# yacc2buss.net
KiCad netlist of a schematic drawn in EAGLE
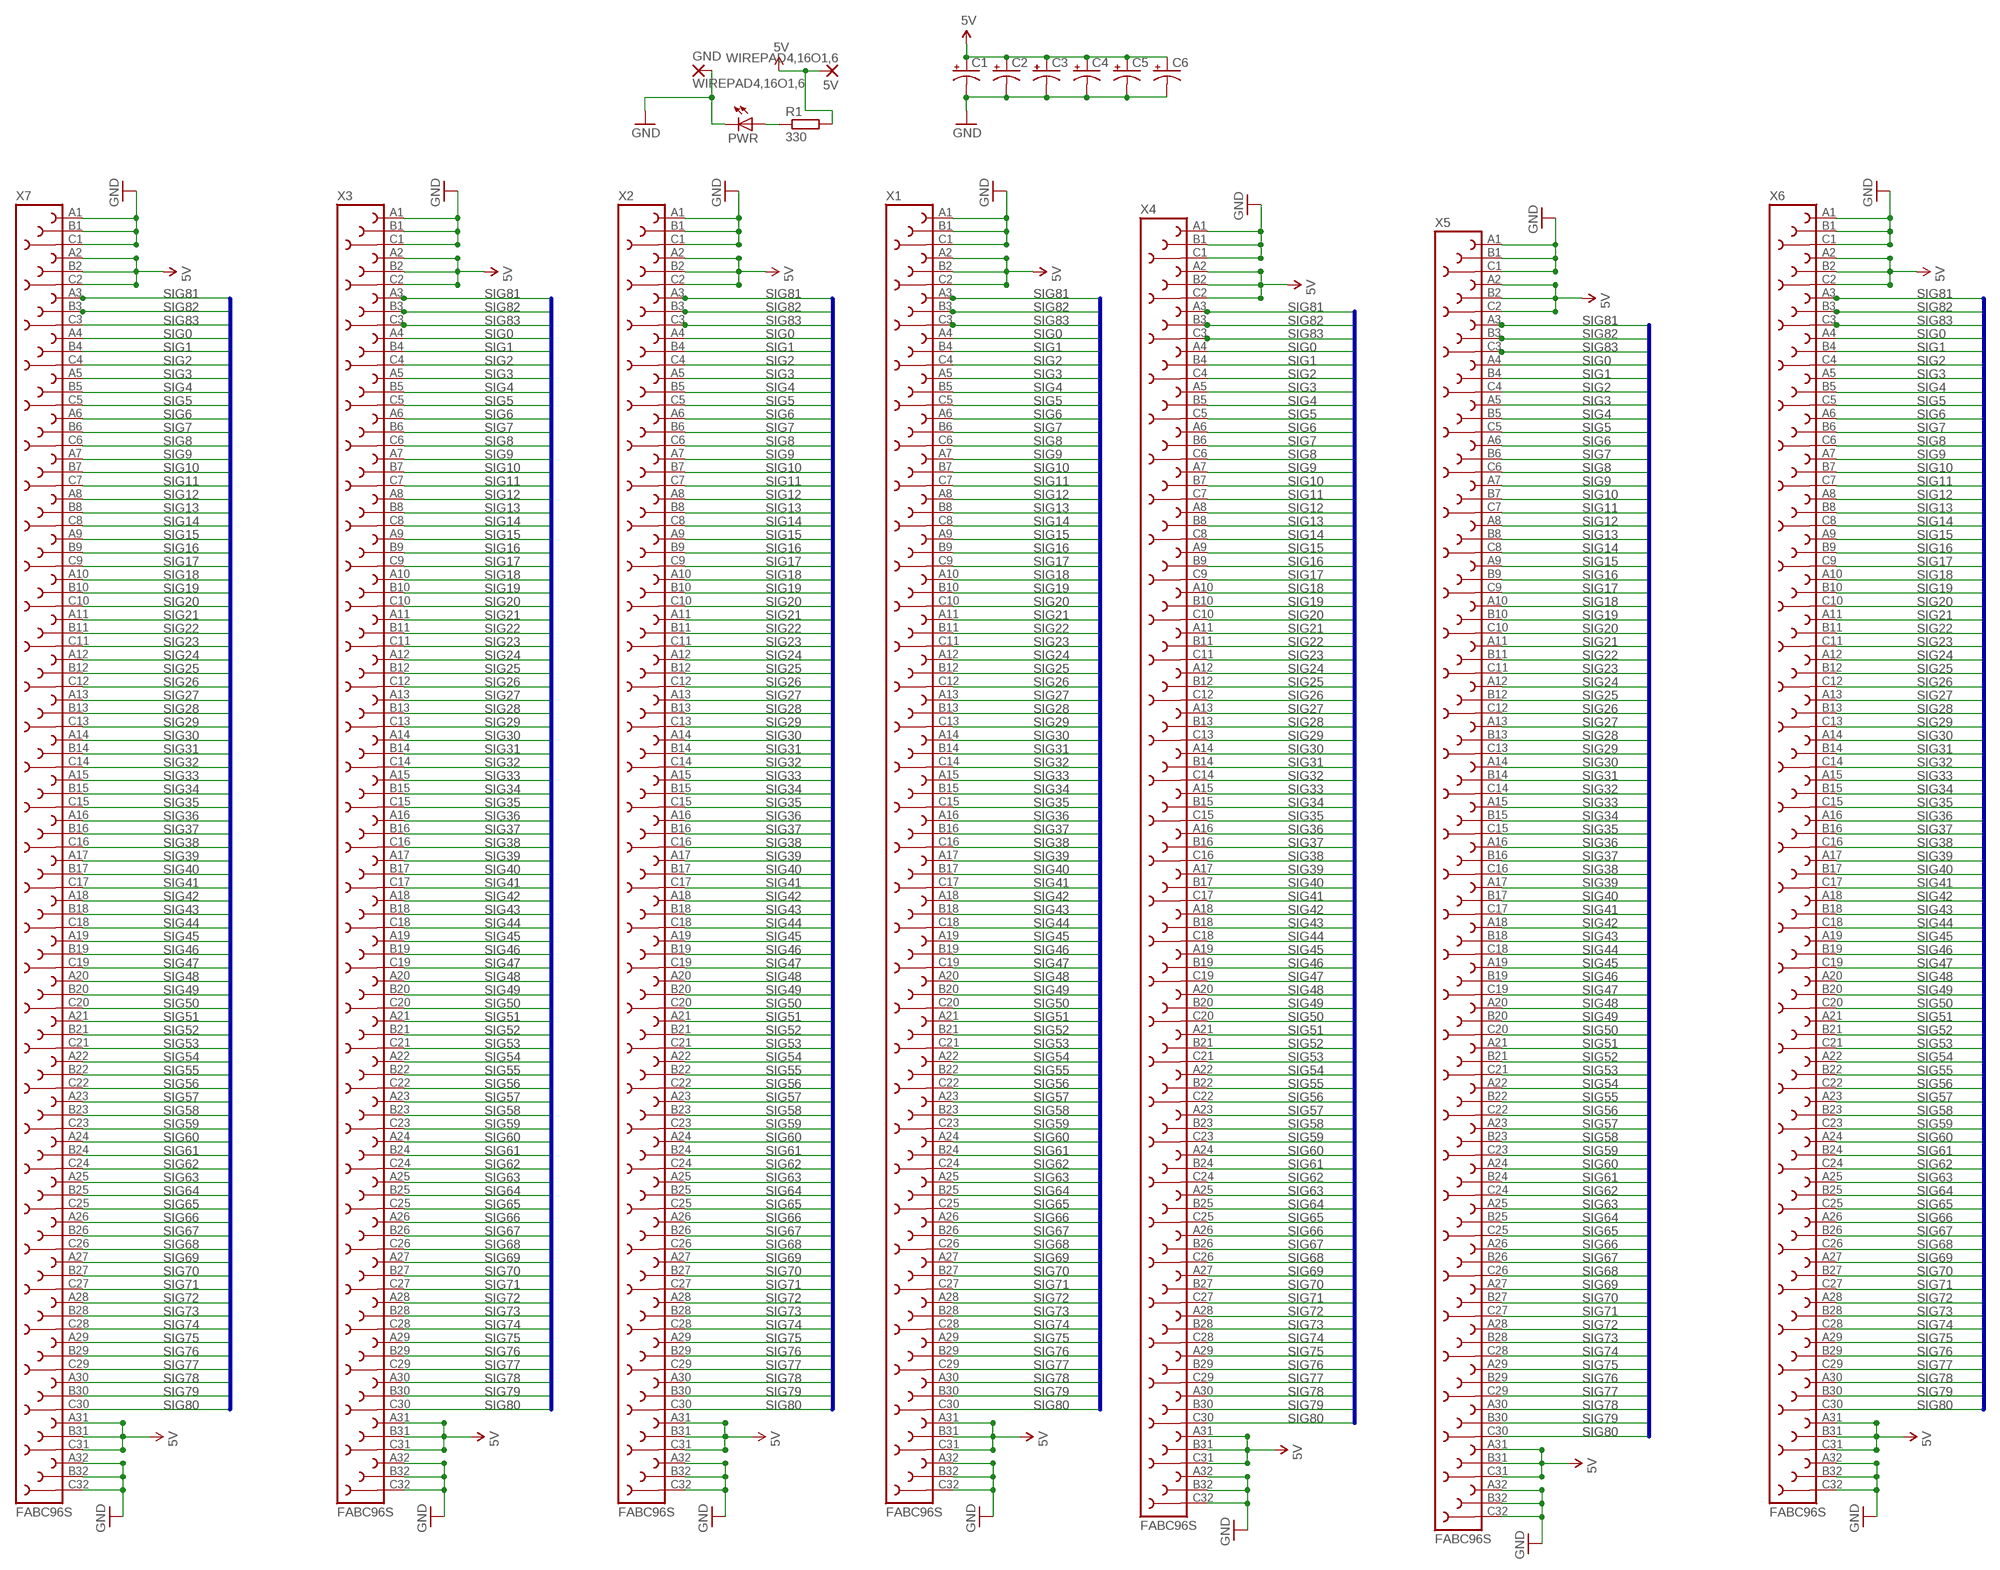
[diagram p0: schematic, sheet 1]

(export (version "E")
  (design (tool "Eeschema 10.0.6"))
  (components
    (comp (ref "5V")
      (value "WIREPAD4,16O1,6")
      (footprint "eagle-import:4,16O1,6")
      (libsource (lib "eagle-import") (part "WIREPAD4,16O1,6"))
    )
    (comp (ref "C1")
      (value "CPOL-USE5-6")
      (footprint "eagle-import:E5-6")
      (libsource (lib "eagle-import") (part "CPOL-USE5-6"))
    )
    (comp (ref "C2")
      (value "CPOL-USE5-6")
      (footprint "eagle-import:E5-6")
      (libsource (lib "eagle-import") (part "CPOL-USE5-6"))
    )
    (comp (ref "C3")
      (value "CPOL-USE5-6")
      (footprint "eagle-import:E5-6")
      (libsource (lib "eagle-import") (part "CPOL-USE5-6"))
    )
    (comp (ref "C4")
      (value "CPOL-USE5-6")
      (footprint "eagle-import:E5-6")
      (libsource (lib "eagle-import") (part "CPOL-USE5-6"))
    )
    (comp (ref "C5")
      (value "CPOL-USE5-6")
      (footprint "eagle-import:E5-6")
      (libsource (lib "eagle-import") (part "CPOL-USE5-6"))
    )
    (comp (ref "C6")
      (value "CPOL-USE5-6")
      (footprint "eagle-import:E5-6")
      (libsource (lib "eagle-import") (part "CPOL-USE5-6"))
    )
    (comp (ref "GND")
      (value "WIREPAD4,16O1,6")
      (footprint "eagle-import:4,16O1,6")
      (libsource (lib "eagle-import") (part "WIREPAD4,16O1,6"))
    )
    (comp (ref "PWR")
      (value "LED5MM")
      (footprint "eagle-import:LED5MM")
      (libsource (lib "eagle-import") (part "LED5MM"))
    )
    (comp (ref "R1")
      (value "330")
      (footprint "eagle-import:0207_10")
      (libsource (lib "eagle-import") (part "R0207/10"))
    )
    (comp (ref "X1")
      (value "FABC96S")
      (footprint "eagle-import:FABC96S")
      (libsource (lib "eagle-import") (part "FABC96S"))
    )
    (comp (ref "X2")
      (value "FABC96S")
      (footprint "eagle-import:FABC96S")
      (libsource (lib "eagle-import") (part "FABC96S"))
    )
    (comp (ref "X3")
      (value "FABC96S")
      (footprint "eagle-import:FABC96S")
      (libsource (lib "eagle-import") (part "FABC96S"))
    )
    (comp (ref "X4")
      (value "FABC96S")
      (footprint "eagle-import:FABC96S")
      (libsource (lib "eagle-import") (part "FABC96S"))
    )
    (comp (ref "X5")
      (value "FABC96S")
      (footprint "eagle-import:FABC96S")
      (libsource (lib "eagle-import") (part "FABC96S"))
    )
    (comp (ref "X6")
      (value "FABC96S")
      (footprint "eagle-import:FABC96S")
      (libsource (lib "eagle-import") (part "FABC96S"))
    )
    (comp (ref "X7")
      (value "FABC96S")
      (footprint "eagle-import:FABC96S")
      (libsource (lib "eagle-import") (part "FABC96S"))
    )
  )
  (nets
    (net (code "1") (name "/SIG0") (class "Default")
      (node (ref "X1") (pin "A4") (pinfunction "A4_A4") (pintype "passive"))
      (node (ref "X2") (pin "A4") (pinfunction "A4_A4") (pintype "passive"))
      (node (ref "X3") (pin "A4") (pinfunction "A4_A4") (pintype "passive"))
      (node (ref "X4") (pin "A4") (pinfunction "A4_A4") (pintype "passive"))
      (node (ref "X5") (pin "A4") (pinfunction "A4_A4") (pintype "passive"))
      (node (ref "X6") (pin "A4") (pinfunction "A4_A4") (pintype "passive"))
      (node (ref "X7") (pin "A4") (pinfunction "A4_A4") (pintype "passive"))
    )
    (net (code "2") (name "/SIG1") (class "Default")
      (node (ref "X1") (pin "B4") (pinfunction "B4_B4") (pintype "passive"))
      (node (ref "X2") (pin "B4") (pinfunction "B4_B4") (pintype "passive"))
      (node (ref "X3") (pin "B4") (pinfunction "B4_B4") (pintype "passive"))
      (node (ref "X4") (pin "B4") (pinfunction "B4_B4") (pintype "passive"))
      (node (ref "X5") (pin "B4") (pinfunction "B4_B4") (pintype "passive"))
      (node (ref "X6") (pin "B4") (pinfunction "B4_B4") (pintype "passive"))
      (node (ref "X7") (pin "B4") (pinfunction "B4_B4") (pintype "passive"))
    )
    (net (code "3") (name "/SIG2") (class "Default")
      (node (ref "X1") (pin "C4") (pinfunction "C4_C4") (pintype "passive"))
      (node (ref "X2") (pin "C4") (pinfunction "C4_C4") (pintype "passive"))
      (node (ref "X3") (pin "C4") (pinfunction "C4_C4") (pintype "passive"))
      (node (ref "X4") (pin "C4") (pinfunction "C4_C4") (pintype "passive"))
      (node (ref "X5") (pin "C4") (pinfunction "C4_C4") (pintype "passive"))
      (node (ref "X6") (pin "C4") (pinfunction "C4_C4") (pintype "passive"))
      (node (ref "X7") (pin "C4") (pinfunction "C4_C4") (pintype "passive"))
    )
    (net (code "4") (name "/SIG3") (class "Default")
      (node (ref "X1") (pin "A5") (pinfunction "A5_A5") (pintype "passive"))
      (node (ref "X2") (pin "A5") (pinfunction "A5_A5") (pintype "passive"))
      (node (ref "X3") (pin "A5") (pinfunction "A5_A5") (pintype "passive"))
      (node (ref "X4") (pin "A5") (pinfunction "A5_A5") (pintype "passive"))
      (node (ref "X5") (pin "A5") (pinfunction "A5_A5") (pintype "passive"))
      (node (ref "X6") (pin "A5") (pinfunction "A5_A5") (pintype "passive"))
      (node (ref "X7") (pin "A5") (pinfunction "A5_A5") (pintype "passive"))
    )
    (net (code "5") (name "/SIG4") (class "Default")
      (node (ref "X1") (pin "B5") (pinfunction "B5_B5") (pintype "passive"))
      (node (ref "X2") (pin "B5") (pinfunction "B5_B5") (pintype "passive"))
      (node (ref "X3") (pin "B5") (pinfunction "B5_B5") (pintype "passive"))
      (node (ref "X4") (pin "B5") (pinfunction "B5_B5") (pintype "passive"))
      (node (ref "X5") (pin "B5") (pinfunction "B5_B5") (pintype "passive"))
      (node (ref "X6") (pin "B5") (pinfunction "B5_B5") (pintype "passive"))
      (node (ref "X7") (pin "B5") (pinfunction "B5_B5") (pintype "passive"))
    )
    (net (code "6") (name "/SIG5") (class "Default")
      (node (ref "X1") (pin "C5") (pinfunction "C5_C5") (pintype "passive"))
      (node (ref "X2") (pin "C5") (pinfunction "C5_C5") (pintype "passive"))
      (node (ref "X3") (pin "C5") (pinfunction "C5_C5") (pintype "passive"))
      (node (ref "X4") (pin "C5") (pinfunction "C5_C5") (pintype "passive"))
      (node (ref "X5") (pin "C5") (pinfunction "C5_C5") (pintype "passive"))
      (node (ref "X6") (pin "C5") (pinfunction "C5_C5") (pintype "passive"))
      (node (ref "X7") (pin "C5") (pinfunction "C5_C5") (pintype "passive"))
    )
    (net (code "7") (name "/SIG6") (class "Default")
      (node (ref "X1") (pin "A6") (pinfunction "A6_A6") (pintype "passive"))
      (node (ref "X2") (pin "A6") (pinfunction "A6_A6") (pintype "passive"))
      (node (ref "X3") (pin "A6") (pinfunction "A6_A6") (pintype "passive"))
      (node (ref "X4") (pin "A6") (pinfunction "A6_A6") (pintype "passive"))
      (node (ref "X5") (pin "A6") (pinfunction "A6_A6") (pintype "passive"))
      (node (ref "X6") (pin "A6") (pinfunction "A6_A6") (pintype "passive"))
      (node (ref "X7") (pin "A6") (pinfunction "A6_A6") (pintype "passive"))
    )
    (net (code "8") (name "/SIG7") (class "Default")
      (node (ref "X1") (pin "B6") (pinfunction "B6_B6") (pintype "passive"))
      (node (ref "X2") (pin "B6") (pinfunction "B6_B6") (pintype "passive"))
      (node (ref "X3") (pin "B6") (pinfunction "B6_B6") (pintype "passive"))
      (node (ref "X4") (pin "B6") (pinfunction "B6_B6") (pintype "passive"))
      (node (ref "X5") (pin "B6") (pinfunction "B6_B6") (pintype "passive"))
      (node (ref "X6") (pin "B6") (pinfunction "B6_B6") (pintype "passive"))
      (node (ref "X7") (pin "B6") (pinfunction "B6_B6") (pintype "passive"))
    )
    (net (code "9") (name "/SIG8") (class "Default")
      (node (ref "X1") (pin "C6") (pinfunction "C6_C6") (pintype "passive"))
      (node (ref "X2") (pin "C6") (pinfunction "C6_C6") (pintype "passive"))
      (node (ref "X3") (pin "C6") (pinfunction "C6_C6") (pintype "passive"))
      (node (ref "X4") (pin "C6") (pinfunction "C6_C6") (pintype "passive"))
      (node (ref "X5") (pin "C6") (pinfunction "C6_C6") (pintype "passive"))
      (node (ref "X6") (pin "C6") (pinfunction "C6_C6") (pintype "passive"))
      (node (ref "X7") (pin "C6") (pinfunction "C6_C6") (pintype "passive"))
    )
    (net (code "10") (name "/SIG9") (class "Default")
      (node (ref "X1") (pin "A7") (pinfunction "A7_A7") (pintype "passive"))
      (node (ref "X2") (pin "A7") (pinfunction "A7_A7") (pintype "passive"))
      (node (ref "X3") (pin "A7") (pinfunction "A7_A7") (pintype "passive"))
      (node (ref "X4") (pin "A7") (pinfunction "A7_A7") (pintype "passive"))
      (node (ref "X5") (pin "A7") (pinfunction "A7_A7") (pintype "passive"))
      (node (ref "X6") (pin "A7") (pinfunction "A7_A7") (pintype "passive"))
      (node (ref "X7") (pin "A7") (pinfunction "A7_A7") (pintype "passive"))
    )
    (net (code "11") (name "/SIG10") (class "Default")
      (node (ref "X1") (pin "B7") (pinfunction "B7_B7") (pintype "passive"))
      (node (ref "X2") (pin "B7") (pinfunction "B7_B7") (pintype "passive"))
      (node (ref "X3") (pin "B7") (pinfunction "B7_B7") (pintype "passive"))
      (node (ref "X4") (pin "B7") (pinfunction "B7_B7") (pintype "passive"))
      (node (ref "X5") (pin "B7") (pinfunction "B7_B7") (pintype "passive"))
      (node (ref "X6") (pin "B7") (pinfunction "B7_B7") (pintype "passive"))
      (node (ref "X7") (pin "B7") (pinfunction "B7_B7") (pintype "passive"))
    )
    (net (code "12") (name "/SIG11") (class "Default")
      (node (ref "X1") (pin "C7") (pinfunction "C7_C7") (pintype "passive"))
      (node (ref "X2") (pin "C7") (pinfunction "C7_C7") (pintype "passive"))
      (node (ref "X3") (pin "C7") (pinfunction "C7_C7") (pintype "passive"))
      (node (ref "X4") (pin "C7") (pinfunction "C7_C7") (pintype "passive"))
      (node (ref "X5") (pin "C7") (pinfunction "C7_C7") (pintype "passive"))
      (node (ref "X6") (pin "C7") (pinfunction "C7_C7") (pintype "passive"))
      (node (ref "X7") (pin "C7") (pinfunction "C7_C7") (pintype "passive"))
    )
    (net (code "13") (name "/SIG12") (class "Default")
      (node (ref "X1") (pin "A8") (pinfunction "A8_A8") (pintype "passive"))
      (node (ref "X2") (pin "A8") (pinfunction "A8_A8") (pintype "passive"))
      (node (ref "X3") (pin "A8") (pinfunction "A8_A8") (pintype "passive"))
      (node (ref "X4") (pin "A8") (pinfunction "A8_A8") (pintype "passive"))
      (node (ref "X5") (pin "A8") (pinfunction "A8_A8") (pintype "passive"))
      (node (ref "X6") (pin "A8") (pinfunction "A8_A8") (pintype "passive"))
      (node (ref "X7") (pin "A8") (pinfunction "A8_A8") (pintype "passive"))
    )
    (net (code "14") (name "/SIG13") (class "Default")
      (node (ref "X1") (pin "B8") (pinfunction "B8_B8") (pintype "passive"))
      (node (ref "X2") (pin "B8") (pinfunction "B8_B8") (pintype "passive"))
      (node (ref "X3") (pin "B8") (pinfunction "B8_B8") (pintype "passive"))
      (node (ref "X4") (pin "B8") (pinfunction "B8_B8") (pintype "passive"))
      (node (ref "X5") (pin "B8") (pinfunction "B8_B8") (pintype "passive"))
      (node (ref "X6") (pin "B8") (pinfunction "B8_B8") (pintype "passive"))
      (node (ref "X7") (pin "B8") (pinfunction "B8_B8") (pintype "passive"))
    )
    (net (code "15") (name "/SIG14") (class "Default")
      (node (ref "X1") (pin "C8") (pinfunction "C8_C8") (pintype "passive"))
      (node (ref "X2") (pin "C8") (pinfunction "C8_C8") (pintype "passive"))
      (node (ref "X3") (pin "C8") (pinfunction "C8_C8") (pintype "passive"))
      (node (ref "X4") (pin "C8") (pinfunction "C8_C8") (pintype "passive"))
      (node (ref "X5") (pin "C8") (pinfunction "C8_C8") (pintype "passive"))
      (node (ref "X6") (pin "C8") (pinfunction "C8_C8") (pintype "passive"))
      (node (ref "X7") (pin "C8") (pinfunction "C8_C8") (pintype "passive"))
    )
    (net (code "16") (name "/SIG15") (class "Default")
      (node (ref "X1") (pin "A9") (pinfunction "A9_A9") (pintype "passive"))
      (node (ref "X2") (pin "A9") (pinfunction "A9_A9") (pintype "passive"))
      (node (ref "X3") (pin "A9") (pinfunction "A9_A9") (pintype "passive"))
      (node (ref "X4") (pin "A9") (pinfunction "A9_A9") (pintype "passive"))
      (node (ref "X5") (pin "A9") (pinfunction "A9_A9") (pintype "passive"))
      (node (ref "X6") (pin "A9") (pinfunction "A9_A9") (pintype "passive"))
      (node (ref "X7") (pin "A9") (pinfunction "A9_A9") (pintype "passive"))
    )
    (net (code "17") (name "/SIG16") (class "Default")
      (node (ref "X1") (pin "B9") (pinfunction "B9_B9") (pintype "passive"))
      (node (ref "X2") (pin "B9") (pinfunction "B9_B9") (pintype "passive"))
      (node (ref "X3") (pin "B9") (pinfunction "B9_B9") (pintype "passive"))
      (node (ref "X4") (pin "B9") (pinfunction "B9_B9") (pintype "passive"))
      (node (ref "X5") (pin "B9") (pinfunction "B9_B9") (pintype "passive"))
      (node (ref "X6") (pin "B9") (pinfunction "B9_B9") (pintype "passive"))
      (node (ref "X7") (pin "B9") (pinfunction "B9_B9") (pintype "passive"))
    )
    (net (code "18") (name "/SIG17") (class "Default")
      (node (ref "X1") (pin "C9") (pinfunction "C9_C9") (pintype "passive"))
      (node (ref "X2") (pin "C9") (pinfunction "C9_C9") (pintype "passive"))
      (node (ref "X3") (pin "C9") (pinfunction "C9_C9") (pintype "passive"))
      (node (ref "X4") (pin "C9") (pinfunction "C9_C9") (pintype "passive"))
      (node (ref "X5") (pin "C9") (pinfunction "C9_C9") (pintype "passive"))
      (node (ref "X6") (pin "C9") (pinfunction "C9_C9") (pintype "passive"))
      (node (ref "X7") (pin "C9") (pinfunction "C9_C9") (pintype "passive"))
    )
    (net (code "19") (name "/SIG18") (class "Default")
      (node (ref "X1") (pin "A10") (pinfunction "A10_A10") (pintype "passive"))
      (node (ref "X2") (pin "A10") (pinfunction "A10_A10") (pintype "passive"))
      (node (ref "X3") (pin "A10") (pinfunction "A10_A10") (pintype "passive"))
      (node (ref "X4") (pin "A10") (pinfunction "A10_A10") (pintype "passive"))
      (node (ref "X5") (pin "A10") (pinfunction "A10_A10") (pintype "passive"))
      (node (ref "X6") (pin "A10") (pinfunction "A10_A10") (pintype "passive"))
      (node (ref "X7") (pin "A10") (pinfunction "A10_A10") (pintype "passive"))
    )
    (net (code "20") (name "/SIG19") (class "Default")
      (node (ref "X1") (pin "B10") (pinfunction "B10_B10") (pintype "passive"))
      (node (ref "X2") (pin "B10") (pinfunction "B10_B10") (pintype "passive"))
      (node (ref "X3") (pin "B10") (pinfunction "B10_B10") (pintype "passive"))
      (node (ref "X4") (pin "B10") (pinfunction "B10_B10") (pintype "passive"))
      (node (ref "X5") (pin "B10") (pinfunction "B10_B10") (pintype "passive"))
      (node (ref "X6") (pin "B10") (pinfunction "B10_B10") (pintype "passive"))
      (node (ref "X7") (pin "B10") (pinfunction "B10_B10") (pintype "passive"))
    )
    (net (code "21") (name "/SIG20") (class "Default")
      (node (ref "X1") (pin "C10") (pinfunction "C10_C10") (pintype "passive"))
      (node (ref "X2") (pin "C10") (pinfunction "C10_C10") (pintype "passive"))
      (node (ref "X3") (pin "C10") (pinfunction "C10_C10") (pintype "passive"))
      (node (ref "X4") (pin "C10") (pinfunction "C10_C10") (pintype "passive"))
      (node (ref "X5") (pin "C10") (pinfunction "C10_C10") (pintype "passive"))
      (node (ref "X6") (pin "C10") (pinfunction "C10_C10") (pintype "passive"))
      (node (ref "X7") (pin "C10") (pinfunction "C10_C10") (pintype "passive"))
    )
    (net (code "22") (name "/SIG21") (class "Default")
      (node (ref "X1") (pin "A11") (pinfunction "A11_A11") (pintype "passive"))
      (node (ref "X2") (pin "A11") (pinfunction "A11_A11") (pintype "passive"))
      (node (ref "X3") (pin "A11") (pinfunction "A11_A11") (pintype "passive"))
      (node (ref "X4") (pin "A11") (pinfunction "A11_A11") (pintype "passive"))
      (node (ref "X5") (pin "A11") (pinfunction "A11_A11") (pintype "passive"))
      (node (ref "X6") (pin "A11") (pinfunction "A11_A11") (pintype "passive"))
      (node (ref "X7") (pin "A11") (pinfunction "A11_A11") (pintype "passive"))
    )
    (net (code "23") (name "/SIG22") (class "Default")
      (node (ref "X1") (pin "B11") (pinfunction "B11_B11") (pintype "passive"))
      (node (ref "X2") (pin "B11") (pinfunction "B11_B11") (pintype "passive"))
      (node (ref "X3") (pin "B11") (pinfunction "B11_B11") (pintype "passive"))
      (node (ref "X4") (pin "B11") (pinfunction "B11_B11") (pintype "passive"))
      (node (ref "X5") (pin "B11") (pinfunction "B11_B11") (pintype "passive"))
      (node (ref "X6") (pin "B11") (pinfunction "B11_B11") (pintype "passive"))
      (node (ref "X7") (pin "B11") (pinfunction "B11_B11") (pintype "passive"))
    )
    (net (code "24") (name "/SIG23") (class "Default")
      (node (ref "X1") (pin "C11") (pinfunction "C11_C11") (pintype "passive"))
      (node (ref "X2") (pin "C11") (pinfunction "C11_C11") (pintype "passive"))
      (node (ref "X3") (pin "C11") (pinfunction "C11_C11") (pintype "passive"))
      (node (ref "X4") (pin "C11") (pinfunction "C11_C11") (pintype "passive"))
      (node (ref "X5") (pin "C11") (pinfunction "C11_C11") (pintype "passive"))
      (node (ref "X6") (pin "C11") (pinfunction "C11_C11") (pintype "passive"))
      (node (ref "X7") (pin "C11") (pinfunction "C11_C11") (pintype "passive"))
    )
    (net (code "25") (name "/SIG24") (class "Default")
      (node (ref "X1") (pin "A12") (pinfunction "A12_A12") (pintype "passive"))
      (node (ref "X2") (pin "A12") (pinfunction "A12_A12") (pintype "passive"))
      (node (ref "X3") (pin "A12") (pinfunction "A12_A12") (pintype "passive"))
      (node (ref "X4") (pin "A12") (pinfunction "A12_A12") (pintype "passive"))
      (node (ref "X5") (pin "A12") (pinfunction "A12_A12") (pintype "passive"))
      (node (ref "X6") (pin "A12") (pinfunction "A12_A12") (pintype "passive"))
      (node (ref "X7") (pin "A12") (pinfunction "A12_A12") (pintype "passive"))
    )
    (net (code "26") (name "/SIG25") (class "Default")
      (node (ref "X1") (pin "B12") (pinfunction "B12_B12") (pintype "passive"))
      (node (ref "X2") (pin "B12") (pinfunction "B12_B12") (pintype "passive"))
      (node (ref "X3") (pin "B12") (pinfunction "B12_B12") (pintype "passive"))
      (node (ref "X4") (pin "B12") (pinfunction "B12_B12") (pintype "passive"))
      (node (ref "X5") (pin "B12") (pinfunction "B12_B12") (pintype "passive"))
      (node (ref "X6") (pin "B12") (pinfunction "B12_B12") (pintype "passive"))
      (node (ref "X7") (pin "B12") (pinfunction "B12_B12") (pintype "passive"))
    )
    (net (code "27") (name "/SIG26") (class "Default")
      (node (ref "X1") (pin "C12") (pinfunction "C12_C12") (pintype "passive"))
      (node (ref "X2") (pin "C12") (pinfunction "C12_C12") (pintype "passive"))
      (node (ref "X3") (pin "C12") (pinfunction "C12_C12") (pintype "passive"))
      (node (ref "X4") (pin "C12") (pinfunction "C12_C12") (pintype "passive"))
      (node (ref "X5") (pin "C12") (pinfunction "C12_C12") (pintype "passive"))
      (node (ref "X6") (pin "C12") (pinfunction "C12_C12") (pintype "passive"))
      (node (ref "X7") (pin "C12") (pinfunction "C12_C12") (pintype "passive"))
    )
    (net (code "28") (name "/SIG27") (class "Default")
      (node (ref "X1") (pin "A13") (pinfunction "A13_A13") (pintype "passive"))
      (node (ref "X2") (pin "A13") (pinfunction "A13_A13") (pintype "passive"))
      (node (ref "X3") (pin "A13") (pinfunction "A13_A13") (pintype "passive"))
      (node (ref "X4") (pin "A13") (pinfunction "A13_A13") (pintype "passive"))
      (node (ref "X5") (pin "A13") (pinfunction "A13_A13") (pintype "passive"))
      (node (ref "X6") (pin "A13") (pinfunction "A13_A13") (pintype "passive"))
      (node (ref "X7") (pin "A13") (pinfunction "A13_A13") (pintype "passive"))
    )
    (net (code "29") (name "/SIG28") (class "Default")
      (node (ref "X1") (pin "B13") (pinfunction "B13_B13") (pintype "passive"))
      (node (ref "X2") (pin "B13") (pinfunction "B13_B13") (pintype "passive"))
      (node (ref "X3") (pin "B13") (pinfunction "B13_B13") (pintype "passive"))
      (node (ref "X4") (pin "B13") (pinfunction "B13_B13") (pintype "passive"))
      (node (ref "X5") (pin "B13") (pinfunction "B13_B13") (pintype "passive"))
      (node (ref "X6") (pin "B13") (pinfunction "B13_B13") (pintype "passive"))
      (node (ref "X7") (pin "B13") (pinfunction "B13_B13") (pintype "passive"))
    )
    (net (code "30") (name "/SIG29") (class "Default")
      (node (ref "X1") (pin "C13") (pinfunction "C13_C13") (pintype "passive"))
      (node (ref "X2") (pin "C13") (pinfunction "C13_C13") (pintype "passive"))
      (node (ref "X3") (pin "C13") (pinfunction "C13_C13") (pintype "passive"))
      (node (ref "X4") (pin "C13") (pinfunction "C13_C13") (pintype "passive"))
      (node (ref "X5") (pin "C13") (pinfunction "C13_C13") (pintype "passive"))
      (node (ref "X6") (pin "C13") (pinfunction "C13_C13") (pintype "passive"))
      (node (ref "X7") (pin "C13") (pinfunction "C13_C13") (pintype "passive"))
    )
    (net (code "31") (name "/SIG30") (class "Default")
      (node (ref "X1") (pin "A14") (pinfunction "A14_A14") (pintype "passive"))
      (node (ref "X2") (pin "A14") (pinfunction "A14_A14") (pintype "passive"))
      (node (ref "X3") (pin "A14") (pinfunction "A14_A14") (pintype "passive"))
      (node (ref "X4") (pin "A14") (pinfunction "A14_A14") (pintype "passive"))
      (node (ref "X5") (pin "A14") (pinfunction "A14_A14") (pintype "passive"))
      (node (ref "X6") (pin "A14") (pinfunction "A14_A14") (pintype "passive"))
      (node (ref "X7") (pin "A14") (pinfunction "A14_A14") (pintype "passive"))
    )
    (net (code "32") (name "/SIG31") (class "Default")
      (node (ref "X1") (pin "B14") (pinfunction "B14_B14") (pintype "passive"))
      (node (ref "X2") (pin "B14") (pinfunction "B14_B14") (pintype "passive"))
      (node (ref "X3") (pin "B14") (pinfunction "B14_B14") (pintype "passive"))
      (node (ref "X4") (pin "B14") (pinfunction "B14_B14") (pintype "passive"))
      (node (ref "X5") (pin "B14") (pinfunction "B14_B14") (pintype "passive"))
      (node (ref "X6") (pin "B14") (pinfunction "B14_B14") (pintype "passive"))
      (node (ref "X7") (pin "B14") (pinfunction "B14_B14") (pintype "passive"))
    )
    (net (code "33") (name "/SIG32") (class "Default")
      (node (ref "X1") (pin "C14") (pinfunction "C14_C14") (pintype "passive"))
      (node (ref "X2") (pin "C14") (pinfunction "C14_C14") (pintype "passive"))
      (node (ref "X3") (pin "C14") (pinfunction "C14_C14") (pintype "passive"))
      (node (ref "X4") (pin "C14") (pinfunction "C14_C14") (pintype "passive"))
      (node (ref "X5") (pin "C14") (pinfunction "C14_C14") (pintype "passive"))
      (node (ref "X6") (pin "C14") (pinfunction "C14_C14") (pintype "passive"))
      (node (ref "X7") (pin "C14") (pinfunction "C14_C14") (pintype "passive"))
    )
    (net (code "34") (name "/SIG33") (class "Default")
      (node (ref "X1") (pin "A15") (pinfunction "A15_A15") (pintype "passive"))
      (node (ref "X2") (pin "A15") (pinfunction "A15_A15") (pintype "passive"))
      (node (ref "X3") (pin "A15") (pinfunction "A15_A15") (pintype "passive"))
      (node (ref "X4") (pin "A15") (pinfunction "A15_A15") (pintype "passive"))
      (node (ref "X5") (pin "A15") (pinfunction "A15_A15") (pintype "passive"))
      (node (ref "X6") (pin "A15") (pinfunction "A15_A15") (pintype "passive"))
      (node (ref "X7") (pin "A15") (pinfunction "A15_A15") (pintype "passive"))
    )
    (net (code "35") (name "/SIG34") (class "Default")
      (node (ref "X1") (pin "B15") (pinfunction "B15_B15") (pintype "passive"))
      (node (ref "X2") (pin "B15") (pinfunction "B15_B15") (pintype "passive"))
      (node (ref "X3") (pin "B15") (pinfunction "B15_B15") (pintype "passive"))
      (node (ref "X4") (pin "B15") (pinfunction "B15_B15") (pintype "passive"))
      (node (ref "X5") (pin "B15") (pinfunction "B15_B15") (pintype "passive"))
      (node (ref "X6") (pin "B15") (pinfunction "B15_B15") (pintype "passive"))
      (node (ref "X7") (pin "B15") (pinfunction "B15_B15") (pintype "passive"))
    )
    (net (code "36") (name "/SIG35") (class "Default")
      (node (ref "X1") (pin "C15") (pinfunction "C15_C15") (pintype "passive"))
      (node (ref "X2") (pin "C15") (pinfunction "C15_C15") (pintype "passive"))
      (node (ref "X3") (pin "C15") (pinfunction "C15_C15") (pintype "passive"))
      (node (ref "X4") (pin "C15") (pinfunction "C15_C15") (pintype "passive"))
      (node (ref "X5") (pin "C15") (pinfunction "C15_C15") (pintype "passive"))
      (node (ref "X6") (pin "C15") (pinfunction "C15_C15") (pintype "passive"))
      (node (ref "X7") (pin "C15") (pinfunction "C15_C15") (pintype "passive"))
    )
    (net (code "37") (name "/SIG36") (class "Default")
      (node (ref "X1") (pin "A16") (pinfunction "A16_A16") (pintype "passive"))
      (node (ref "X2") (pin "A16") (pinfunction "A16_A16") (pintype "passive"))
      (node (ref "X3") (pin "A16") (pinfunction "A16_A16") (pintype "passive"))
      (node (ref "X4") (pin "A16") (pinfunction "A16_A16") (pintype "passive"))
      (node (ref "X5") (pin "A16") (pinfunction "A16_A16") (pintype "passive"))
      (node (ref "X6") (pin "A16") (pinfunction "A16_A16") (pintype "passive"))
      (node (ref "X7") (pin "A16") (pinfunction "A16_A16") (pintype "passive"))
    )
    (net (code "38") (name "/SIG37") (class "Default")
      (node (ref "X1") (pin "B16") (pinfunction "B16_B16") (pintype "passive"))
      (node (ref "X2") (pin "B16") (pinfunction "B16_B16") (pintype "passive"))
      (node (ref "X3") (pin "B16") (pinfunction "B16_B16") (pintype "passive"))
      (node (ref "X4") (pin "B16") (pinfunction "B16_B16") (pintype "passive"))
      (node (ref "X5") (pin "B16") (pinfunction "B16_B16") (pintype "passive"))
      (node (ref "X6") (pin "B16") (pinfunction "B16_B16") (pintype "passive"))
      (node (ref "X7") (pin "B16") (pinfunction "B16_B16") (pintype "passive"))
    )
    (net (code "39") (name "/SIG38") (class "Default")
      (node (ref "X1") (pin "C16") (pinfunction "C16_C16") (pintype "passive"))
      (node (ref "X2") (pin "C16") (pinfunction "C16_C16") (pintype "passive"))
      (node (ref "X3") (pin "C16") (pinfunction "C16_C16") (pintype "passive"))
      (node (ref "X4") (pin "C16") (pinfunction "C16_C16") (pintype "passive"))
      (node (ref "X5") (pin "C16") (pinfunction "C16_C16") (pintype "passive"))
      (node (ref "X6") (pin "C16") (pinfunction "C16_C16") (pintype "passive"))
      (node (ref "X7") (pin "C16") (pinfunction "C16_C16") (pintype "passive"))
    )
    (net (code "40") (name "/SIG39") (class "Default")
      (node (ref "X1") (pin "A17") (pinfunction "A17_A17") (pintype "passive"))
      (node (ref "X2") (pin "A17") (pinfunction "A17_A17") (pintype "passive"))
      (node (ref "X3") (pin "A17") (pinfunction "A17_A17") (pintype "passive"))
      (node (ref "X4") (pin "A17") (pinfunction "A17_A17") (pintype "passive"))
      (node (ref "X5") (pin "A17") (pinfunction "A17_A17") (pintype "passive"))
      (node (ref "X6") (pin "A17") (pinfunction "A17_A17") (pintype "passive"))
      (node (ref "X7") (pin "A17") (pinfunction "A17_A17") (pintype "passive"))
    )
    (net (code "41") (name "/SIG40") (class "Default")
      (node (ref "X1") (pin "B17") (pinfunction "B17_B17") (pintype "passive"))
      (node (ref "X2") (pin "B17") (pinfunction "B17_B17") (pintype "passive"))
      (node (ref "X3") (pin "B17") (pinfunction "B17_B17") (pintype "passive"))
      (node (ref "X4") (pin "B17") (pinfunction "B17_B17") (pintype "passive"))
      (node (ref "X5") (pin "B17") (pinfunction "B17_B17") (pintype "passive"))
      (node (ref "X6") (pin "B17") (pinfunction "B17_B17") (pintype "passive"))
      (node (ref "X7") (pin "B17") (pinfunction "B17_B17") (pintype "passive"))
    )
    (net (code "42") (name "/SIG41") (class "Default")
      (node (ref "X1") (pin "C17") (pinfunction "C17_C17") (pintype "passive"))
      (node (ref "X2") (pin "C17") (pinfunction "C17_C17") (pintype "passive"))
      (node (ref "X3") (pin "C17") (pinfunction "C17_C17") (pintype "passive"))
      (node (ref "X4") (pin "C17") (pinfunction "C17_C17") (pintype "passive"))
      (node (ref "X5") (pin "C17") (pinfunction "C17_C17") (pintype "passive"))
      (node (ref "X6") (pin "C17") (pinfunction "C17_C17") (pintype "passive"))
      (node (ref "X7") (pin "C17") (pinfunction "C17_C17") (pintype "passive"))
    )
    (net (code "43") (name "/SIG42") (class "Default")
      (node (ref "X1") (pin "A18") (pinfunction "A18_A18") (pintype "passive"))
      (node (ref "X2") (pin "A18") (pinfunction "A18_A18") (pintype "passive"))
      (node (ref "X3") (pin "A18") (pinfunction "A18_A18") (pintype "passive"))
      (node (ref "X4") (pin "A18") (pinfunction "A18_A18") (pintype "passive"))
      (node (ref "X5") (pin "A18") (pinfunction "A18_A18") (pintype "passive"))
      (node (ref "X6") (pin "A18") (pinfunction "A18_A18") (pintype "passive"))
      (node (ref "X7") (pin "A18") (pinfunction "A18_A18") (pintype "passive"))
    )
    (net (code "44") (name "/SIG43") (class "Default")
      (node (ref "X1") (pin "B18") (pinfunction "B18_B18") (pintype "passive"))
      (node (ref "X2") (pin "B18") (pinfunction "B18_B18") (pintype "passive"))
      (node (ref "X3") (pin "B18") (pinfunction "B18_B18") (pintype "passive"))
      (node (ref "X4") (pin "B18") (pinfunction "B18_B18") (pintype "passive"))
      (node (ref "X5") (pin "B18") (pinfunction "B18_B18") (pintype "passive"))
      (node (ref "X6") (pin "B18") (pinfunction "B18_B18") (pintype "passive"))
      (node (ref "X7") (pin "B18") (pinfunction "B18_B18") (pintype "passive"))
    )
    (net (code "45") (name "/SIG44") (class "Default")
      (node (ref "X1") (pin "C18") (pinfunction "C18_C18") (pintype "passive"))
      (node (ref "X2") (pin "C18") (pinfunction "C18_C18") (pintype "passive"))
      (node (ref "X3") (pin "C18") (pinfunction "C18_C18") (pintype "passive"))
      (node (ref "X4") (pin "C18") (pinfunction "C18_C18") (pintype "passive"))
      (node (ref "X5") (pin "C18") (pinfunction "C18_C18") (pintype "passive"))
      (node (ref "X6") (pin "C18") (pinfunction "C18_C18") (pintype "passive"))
      (node (ref "X7") (pin "C18") (pinfunction "C18_C18") (pintype "passive"))
    )
    (net (code "46") (name "/SIG45") (class "Default")
      (node (ref "X1") (pin "A19") (pinfunction "A19_A19") (pintype "passive"))
      (node (ref "X2") (pin "A19") (pinfunction "A19_A19") (pintype "passive"))
      (node (ref "X3") (pin "A19") (pinfunction "A19_A19") (pintype "passive"))
      (node (ref "X4") (pin "A19") (pinfunction "A19_A19") (pintype "passive"))
      (node (ref "X5") (pin "A19") (pinfunction "A19_A19") (pintype "passive"))
      (node (ref "X6") (pin "A19") (pinfunction "A19_A19") (pintype "passive"))
      (node (ref "X7") (pin "A19") (pinfunction "A19_A19") (pintype "passive"))
    )
    (net (code "47") (name "/SIG46") (class "Default")
      (node (ref "X1") (pin "B19") (pinfunction "B19_B19") (pintype "passive"))
      (node (ref "X2") (pin "B19") (pinfunction "B19_B19") (pintype "passive"))
      (node (ref "X3") (pin "B19") (pinfunction "B19_B19") (pintype "passive"))
      (node (ref "X4") (pin "B19") (pinfunction "B19_B19") (pintype "passive"))
      (node (ref "X5") (pin "B19") (pinfunction "B19_B19") (pintype "passive"))
      (node (ref "X6") (pin "B19") (pinfunction "B19_B19") (pintype "passive"))
      (node (ref "X7") (pin "B19") (pinfunction "B19_B19") (pintype "passive"))
    )
    (net (code "48") (name "/SIG47") (class "Default")
      (node (ref "X1") (pin "C19") (pinfunction "C19_C19") (pintype "passive"))
      (node (ref "X2") (pin "C19") (pinfunction "C19_C19") (pintype "passive"))
      (node (ref "X3") (pin "C19") (pinfunction "C19_C19") (pintype "passive"))
      (node (ref "X4") (pin "C19") (pinfunction "C19_C19") (pintype "passive"))
      (node (ref "X5") (pin "C19") (pinfunction "C19_C19") (pintype "passive"))
      (node (ref "X6") (pin "C19") (pinfunction "C19_C19") (pintype "passive"))
      (node (ref "X7") (pin "C19") (pinfunction "C19_C19") (pintype "passive"))
    )
    (net (code "49") (name "/SIG48") (class "Default")
      (node (ref "X1") (pin "A20") (pinfunction "A20_A20") (pintype "passive"))
      (node (ref "X2") (pin "A20") (pinfunction "A20_A20") (pintype "passive"))
      (node (ref "X3") (pin "A20") (pinfunction "A20_A20") (pintype "passive"))
      (node (ref "X4") (pin "A20") (pinfunction "A20_A20") (pintype "passive"))
      (node (ref "X5") (pin "A20") (pinfunction "A20_A20") (pintype "passive"))
      (node (ref "X6") (pin "A20") (pinfunction "A20_A20") (pintype "passive"))
      (node (ref "X7") (pin "A20") (pinfunction "A20_A20") (pintype "passive"))
    )
    (net (code "50") (name "/SIG49") (class "Default")
      (node (ref "X1") (pin "B20") (pinfunction "B20_B20") (pintype "passive"))
      (node (ref "X2") (pin "B20") (pinfunction "B20_B20") (pintype "passive"))
      (node (ref "X3") (pin "B20") (pinfunction "B20_B20") (pintype "passive"))
      (node (ref "X4") (pin "B20") (pinfunction "B20_B20") (pintype "passive"))
      (node (ref "X5") (pin "B20") (pinfunction "B20_B20") (pintype "passive"))
      (node (ref "X6") (pin "B20") (pinfunction "B20_B20") (pintype "passive"))
      (node (ref "X7") (pin "B20") (pinfunction "B20_B20") (pintype "passive"))
    )
    (net (code "51") (name "/SIG50") (class "Default")
      (node (ref "X1") (pin "C20") (pinfunction "C20_C20") (pintype "passive"))
      (node (ref "X2") (pin "C20") (pinfunction "C20_C20") (pintype "passive"))
      (node (ref "X3") (pin "C20") (pinfunction "C20_C20") (pintype "passive"))
      (node (ref "X4") (pin "C20") (pinfunction "C20_C20") (pintype "passive"))
      (node (ref "X5") (pin "C20") (pinfunction "C20_C20") (pintype "passive"))
      (node (ref "X6") (pin "C20") (pinfunction "C20_C20") (pintype "passive"))
      (node (ref "X7") (pin "C20") (pinfunction "C20_C20") (pintype "passive"))
    )
    (net (code "52") (name "/SIG51") (class "Default")
      (node (ref "X1") (pin "A21") (pinfunction "A21_A21") (pintype "passive"))
      (node (ref "X2") (pin "A21") (pinfunction "A21_A21") (pintype "passive"))
      (node (ref "X3") (pin "A21") (pinfunction "A21_A21") (pintype "passive"))
      (node (ref "X4") (pin "A21") (pinfunction "A21_A21") (pintype "passive"))
      (node (ref "X5") (pin "A21") (pinfunction "A21_A21") (pintype "passive"))
      (node (ref "X6") (pin "A21") (pinfunction "A21_A21") (pintype "passive"))
      (node (ref "X7") (pin "A21") (pinfunction "A21_A21") (pintype "passive"))
    )
    (net (code "53") (name "/SIG52") (class "Default")
      (node (ref "X1") (pin "B21") (pinfunction "B21_B21") (pintype "passive"))
      (node (ref "X2") (pin "B21") (pinfunction "B21_B21") (pintype "passive"))
      (node (ref "X3") (pin "B21") (pinfunction "B21_B21") (pintype "passive"))
      (node (ref "X4") (pin "B21") (pinfunction "B21_B21") (pintype "passive"))
      (node (ref "X5") (pin "B21") (pinfunction "B21_B21") (pintype "passive"))
      (node (ref "X6") (pin "B21") (pinfunction "B21_B21") (pintype "passive"))
      (node (ref "X7") (pin "B21") (pinfunction "B21_B21") (pintype "passive"))
    )
    (net (code "54") (name "/SIG53") (class "Default")
      (node (ref "X1") (pin "C21") (pinfunction "C21_C21") (pintype "passive"))
      (node (ref "X2") (pin "C21") (pinfunction "C21_C21") (pintype "passive"))
      (node (ref "X3") (pin "C21") (pinfunction "C21_C21") (pintype "passive"))
      (node (ref "X4") (pin "C21") (pinfunction "C21_C21") (pintype "passive"))
      (node (ref "X5") (pin "C21") (pinfunction "C21_C21") (pintype "passive"))
      (node (ref "X6") (pin "C21") (pinfunction "C21_C21") (pintype "passive"))
      (node (ref "X7") (pin "C21") (pinfunction "C21_C21") (pintype "passive"))
    )
    (net (code "55") (name "/SIG54") (class "Default")
      (node (ref "X1") (pin "A22") (pinfunction "A22_A22") (pintype "passive"))
      (node (ref "X2") (pin "A22") (pinfunction "A22_A22") (pintype "passive"))
      (node (ref "X3") (pin "A22") (pinfunction "A22_A22") (pintype "passive"))
      (node (ref "X4") (pin "A22") (pinfunction "A22_A22") (pintype "passive"))
      (node (ref "X5") (pin "A22") (pinfunction "A22_A22") (pintype "passive"))
      (node (ref "X6") (pin "A22") (pinfunction "A22_A22") (pintype "passive"))
      (node (ref "X7") (pin "A22") (pinfunction "A22_A22") (pintype "passive"))
    )
    (net (code "56") (name "/SIG55") (class "Default")
      (node (ref "X1") (pin "B22") (pinfunction "B22_B22") (pintype "passive"))
      (node (ref "X2") (pin "B22") (pinfunction "B22_B22") (pintype "passive"))
      (node (ref "X3") (pin "B22") (pinfunction "B22_B22") (pintype "passive"))
      (node (ref "X4") (pin "B22") (pinfunction "B22_B22") (pintype "passive"))
      (node (ref "X5") (pin "B22") (pinfunction "B22_B22") (pintype "passive"))
      (node (ref "X6") (pin "B22") (pinfunction "B22_B22") (pintype "passive"))
      (node (ref "X7") (pin "B22") (pinfunction "B22_B22") (pintype "passive"))
    )
    (net (code "57") (name "/SIG56") (class "Default")
      (node (ref "X1") (pin "C22") (pinfunction "C22_C22") (pintype "passive"))
      (node (ref "X2") (pin "C22") (pinfunction "C22_C22") (pintype "passive"))
      (node (ref "X3") (pin "C22") (pinfunction "C22_C22") (pintype "passive"))
      (node (ref "X4") (pin "C22") (pinfunction "C22_C22") (pintype "passive"))
      (node (ref "X5") (pin "C22") (pinfunction "C22_C22") (pintype "passive"))
      (node (ref "X6") (pin "C22") (pinfunction "C22_C22") (pintype "passive"))
      (node (ref "X7") (pin "C22") (pinfunction "C22_C22") (pintype "passive"))
    )
    (net (code "58") (name "/SIG57") (class "Default")
      (node (ref "X1") (pin "A23") (pinfunction "A23_A23") (pintype "passive"))
      (node (ref "X2") (pin "A23") (pinfunction "A23_A23") (pintype "passive"))
      (node (ref "X3") (pin "A23") (pinfunction "A23_A23") (pintype "passive"))
      (node (ref "X4") (pin "A23") (pinfunction "A23_A23") (pintype "passive"))
      (node (ref "X5") (pin "A23") (pinfunction "A23_A23") (pintype "passive"))
      (node (ref "X6") (pin "A23") (pinfunction "A23_A23") (pintype "passive"))
      (node (ref "X7") (pin "A23") (pinfunction "A23_A23") (pintype "passive"))
    )
    (net (code "59") (name "/SIG58") (class "Default")
      (node (ref "X1") (pin "B23") (pinfunction "B23_B23") (pintype "passive"))
      (node (ref "X2") (pin "B23") (pinfunction "B23_B23") (pintype "passive"))
      (node (ref "X3") (pin "B23") (pinfunction "B23_B23") (pintype "passive"))
      (node (ref "X4") (pin "B23") (pinfunction "B23_B23") (pintype "passive"))
      (node (ref "X5") (pin "B23") (pinfunction "B23_B23") (pintype "passive"))
      (node (ref "X6") (pin "B23") (pinfunction "B23_B23") (pintype "passive"))
      (node (ref "X7") (pin "B23") (pinfunction "B23_B23") (pintype "passive"))
    )
    (net (code "60") (name "/SIG59") (class "Default")
      (node (ref "X1") (pin "C23") (pinfunction "C23_C23") (pintype "passive"))
      (node (ref "X2") (pin "C23") (pinfunction "C23_C23") (pintype "passive"))
      (node (ref "X3") (pin "C23") (pinfunction "C23_C23") (pintype "passive"))
      (node (ref "X4") (pin "C23") (pinfunction "C23_C23") (pintype "passive"))
      (node (ref "X5") (pin "C23") (pinfunction "C23_C23") (pintype "passive"))
      (node (ref "X6") (pin "C23") (pinfunction "C23_C23") (pintype "passive"))
      (node (ref "X7") (pin "C23") (pinfunction "C23_C23") (pintype "passive"))
    )
    (net (code "61") (name "/SIG60") (class "Default")
      (node (ref "X1") (pin "A24") (pinfunction "A24_A24") (pintype "passive"))
      (node (ref "X2") (pin "A24") (pinfunction "A24_A24") (pintype "passive"))
      (node (ref "X3") (pin "A24") (pinfunction "A24_A24") (pintype "passive"))
      (node (ref "X4") (pin "A24") (pinfunction "A24_A24") (pintype "passive"))
      (node (ref "X5") (pin "A24") (pinfunction "A24_A24") (pintype "passive"))
      (node (ref "X6") (pin "A24") (pinfunction "A24_A24") (pintype "passive"))
      (node (ref "X7") (pin "A24") (pinfunction "A24_A24") (pintype "passive"))
    )
    (net (code "62") (name "/SIG61") (class "Default")
      (node (ref "X1") (pin "B24") (pinfunction "B24_B24") (pintype "passive"))
      (node (ref "X2") (pin "B24") (pinfunction "B24_B24") (pintype "passive"))
      (node (ref "X3") (pin "B24") (pinfunction "B24_B24") (pintype "passive"))
      (node (ref "X4") (pin "B24") (pinfunction "B24_B24") (pintype "passive"))
      (node (ref "X5") (pin "B24") (pinfunction "B24_B24") (pintype "passive"))
      (node (ref "X6") (pin "B24") (pinfunction "B24_B24") (pintype "passive"))
      (node (ref "X7") (pin "B24") (pinfunction "B24_B24") (pintype "passive"))
    )
    (net (code "63") (name "/SIG62") (class "Default")
      (node (ref "X1") (pin "C24") (pinfunction "C24_C24") (pintype "passive"))
      (node (ref "X2") (pin "C24") (pinfunction "C24_C24") (pintype "passive"))
      (node (ref "X3") (pin "C24") (pinfunction "C24_C24") (pintype "passive"))
      (node (ref "X4") (pin "C24") (pinfunction "C24_C24") (pintype "passive"))
      (node (ref "X5") (pin "C24") (pinfunction "C24_C24") (pintype "passive"))
      (node (ref "X6") (pin "C24") (pinfunction "C24_C24") (pintype "passive"))
      (node (ref "X7") (pin "C24") (pinfunction "C24_C24") (pintype "passive"))
    )
    (net (code "64") (name "/SIG63") (class "Default")
      (node (ref "X1") (pin "A25") (pinfunction "A25_A25") (pintype "passive"))
      (node (ref "X2") (pin "A25") (pinfunction "A25_A25") (pintype "passive"))
      (node (ref "X3") (pin "A25") (pinfunction "A25_A25") (pintype "passive"))
      (node (ref "X4") (pin "A25") (pinfunction "A25_A25") (pintype "passive"))
      (node (ref "X5") (pin "A25") (pinfunction "A25_A25") (pintype "passive"))
      (node (ref "X6") (pin "A25") (pinfunction "A25_A25") (pintype "passive"))
      (node (ref "X7") (pin "A25") (pinfunction "A25_A25") (pintype "passive"))
    )
    (net (code "65") (name "/SIG64") (class "Default")
      (node (ref "X1") (pin "B25") (pinfunction "B25_B25") (pintype "passive"))
      (node (ref "X2") (pin "B25") (pinfunction "B25_B25") (pintype "passive"))
      (node (ref "X3") (pin "B25") (pinfunction "B25_B25") (pintype "passive"))
      (node (ref "X4") (pin "B25") (pinfunction "B25_B25") (pintype "passive"))
      (node (ref "X5") (pin "B25") (pinfunction "B25_B25") (pintype "passive"))
      (node (ref "X6") (pin "B25") (pinfunction "B25_B25") (pintype "passive"))
      (node (ref "X7") (pin "B25") (pinfunction "B25_B25") (pintype "passive"))
    )
    (net (code "66") (name "/SIG65") (class "Default")
      (node (ref "X1") (pin "C25") (pinfunction "C25_C25") (pintype "passive"))
      (node (ref "X2") (pin "C25") (pinfunction "C25_C25") (pintype "passive"))
      (node (ref "X3") (pin "C25") (pinfunction "C25_C25") (pintype "passive"))
      (node (ref "X4") (pin "C25") (pinfunction "C25_C25") (pintype "passive"))
      (node (ref "X5") (pin "C25") (pinfunction "C25_C25") (pintype "passive"))
      (node (ref "X6") (pin "C25") (pinfunction "C25_C25") (pintype "passive"))
      (node (ref "X7") (pin "C25") (pinfunction "C25_C25") (pintype "passive"))
    )
    (net (code "67") (name "/SIG66") (class "Default")
      (node (ref "X1") (pin "A26") (pinfunction "A26_A26") (pintype "passive"))
      (node (ref "X2") (pin "A26") (pinfunction "A26_A26") (pintype "passive"))
      (node (ref "X3") (pin "A26") (pinfunction "A26_A26") (pintype "passive"))
      (node (ref "X4") (pin "A26") (pinfunction "A26_A26") (pintype "passive"))
      (node (ref "X5") (pin "A26") (pinfunction "A26_A26") (pintype "passive"))
      (node (ref "X6") (pin "A26") (pinfunction "A26_A26") (pintype "passive"))
      (node (ref "X7") (pin "A26") (pinfunction "A26_A26") (pintype "passive"))
    )
    (net (code "68") (name "/SIG67") (class "Default")
      (node (ref "X1") (pin "B26") (pinfunction "B26_B26") (pintype "passive"))
      (node (ref "X2") (pin "B26") (pinfunction "B26_B26") (pintype "passive"))
      (node (ref "X3") (pin "B26") (pinfunction "B26_B26") (pintype "passive"))
      (node (ref "X4") (pin "B26") (pinfunction "B26_B26") (pintype "passive"))
      (node (ref "X5") (pin "B26") (pinfunction "B26_B26") (pintype "passive"))
      (node (ref "X6") (pin "B26") (pinfunction "B26_B26") (pintype "passive"))
      (node (ref "X7") (pin "B26") (pinfunction "B26_B26") (pintype "passive"))
    )
    (net (code "69") (name "/SIG68") (class "Default")
      (node (ref "X1") (pin "C26") (pinfunction "C26_C26") (pintype "passive"))
      (node (ref "X2") (pin "C26") (pinfunction "C26_C26") (pintype "passive"))
      (node (ref "X3") (pin "C26") (pinfunction "C26_C26") (pintype "passive"))
      (node (ref "X4") (pin "C26") (pinfunction "C26_C26") (pintype "passive"))
      (node (ref "X5") (pin "C26") (pinfunction "C26_C26") (pintype "passive"))
      (node (ref "X6") (pin "C26") (pinfunction "C26_C26") (pintype "passive"))
      (node (ref "X7") (pin "C26") (pinfunction "C26_C26") (pintype "passive"))
    )
    (net (code "70") (name "/SIG69") (class "Default")
      (node (ref "X1") (pin "A27") (pinfunction "A27_A27") (pintype "passive"))
      (node (ref "X2") (pin "A27") (pinfunction "A27_A27") (pintype "passive"))
      (node (ref "X3") (pin "A27") (pinfunction "A27_A27") (pintype "passive"))
      (node (ref "X4") (pin "A27") (pinfunction "A27_A27") (pintype "passive"))
      (node (ref "X5") (pin "A27") (pinfunction "A27_A27") (pintype "passive"))
      (node (ref "X6") (pin "A27") (pinfunction "A27_A27") (pintype "passive"))
      (node (ref "X7") (pin "A27") (pinfunction "A27_A27") (pintype "passive"))
    )
    (net (code "71") (name "/SIG70") (class "Default")
      (node (ref "X1") (pin "B27") (pinfunction "B27_B27") (pintype "passive"))
      (node (ref "X2") (pin "B27") (pinfunction "B27_B27") (pintype "passive"))
      (node (ref "X3") (pin "B27") (pinfunction "B27_B27") (pintype "passive"))
      (node (ref "X4") (pin "B27") (pinfunction "B27_B27") (pintype "passive"))
      (node (ref "X5") (pin "B27") (pinfunction "B27_B27") (pintype "passive"))
      (node (ref "X6") (pin "B27") (pinfunction "B27_B27") (pintype "passive"))
      (node (ref "X7") (pin "B27") (pinfunction "B27_B27") (pintype "passive"))
    )
    (net (code "72") (name "/SIG71") (class "Default")
      (node (ref "X1") (pin "C27") (pinfunction "C27_C27") (pintype "passive"))
      (node (ref "X2") (pin "C27") (pinfunction "C27_C27") (pintype "passive"))
      (node (ref "X3") (pin "C27") (pinfunction "C27_C27") (pintype "passive"))
      (node (ref "X4") (pin "C27") (pinfunction "C27_C27") (pintype "passive"))
      (node (ref "X5") (pin "C27") (pinfunction "C27_C27") (pintype "passive"))
      (node (ref "X6") (pin "C27") (pinfunction "C27_C27") (pintype "passive"))
      (node (ref "X7") (pin "C27") (pinfunction "C27_C27") (pintype "passive"))
    )
    (net (code "73") (name "/SIG72") (class "Default")
      (node (ref "X1") (pin "A28") (pinfunction "A28_A28") (pintype "passive"))
      (node (ref "X2") (pin "A28") (pinfunction "A28_A28") (pintype "passive"))
      (node (ref "X3") (pin "A28") (pinfunction "A28_A28") (pintype "passive"))
      (node (ref "X4") (pin "A28") (pinfunction "A28_A28") (pintype "passive"))
      (node (ref "X5") (pin "A28") (pinfunction "A28_A28") (pintype "passive"))
      (node (ref "X6") (pin "A28") (pinfunction "A28_A28") (pintype "passive"))
      (node (ref "X7") (pin "A28") (pinfunction "A28_A28") (pintype "passive"))
    )
    (net (code "74") (name "/SIG73") (class "Default")
      (node (ref "X1") (pin "B28") (pinfunction "B28_B28") (pintype "passive"))
      (node (ref "X2") (pin "B28") (pinfunction "B28_B28") (pintype "passive"))
      (node (ref "X3") (pin "B28") (pinfunction "B28_B28") (pintype "passive"))
      (node (ref "X4") (pin "B28") (pinfunction "B28_B28") (pintype "passive"))
      (node (ref "X5") (pin "B28") (pinfunction "B28_B28") (pintype "passive"))
      (node (ref "X6") (pin "B28") (pinfunction "B28_B28") (pintype "passive"))
      (node (ref "X7") (pin "B28") (pinfunction "B28_B28") (pintype "passive"))
    )
    (net (code "75") (name "/SIG74") (class "Default")
      (node (ref "X1") (pin "C28") (pinfunction "C28_C28") (pintype "passive"))
      (node (ref "X2") (pin "C28") (pinfunction "C28_C28") (pintype "passive"))
      (node (ref "X3") (pin "C28") (pinfunction "C28_C28") (pintype "passive"))
      (node (ref "X4") (pin "C28") (pinfunction "C28_C28") (pintype "passive"))
      (node (ref "X5") (pin "C28") (pinfunction "C28_C28") (pintype "passive"))
      (node (ref "X6") (pin "C28") (pinfunction "C28_C28") (pintype "passive"))
      (node (ref "X7") (pin "C28") (pinfunction "C28_C28") (pintype "passive"))
    )
    (net (code "76") (name "/SIG75") (class "Default")
      (node (ref "X1") (pin "A29") (pinfunction "A29_A29") (pintype "passive"))
      (node (ref "X2") (pin "A29") (pinfunction "A29_A29") (pintype "passive"))
      (node (ref "X3") (pin "A29") (pinfunction "A29_A29") (pintype "passive"))
      (node (ref "X4") (pin "A29") (pinfunction "A29_A29") (pintype "passive"))
      (node (ref "X5") (pin "A29") (pinfunction "A29_A29") (pintype "passive"))
      (node (ref "X6") (pin "A29") (pinfunction "A29_A29") (pintype "passive"))
      (node (ref "X7") (pin "A29") (pinfunction "A29_A29") (pintype "passive"))
    )
    (net (code "77") (name "/SIG76") (class "Default")
      (node (ref "X1") (pin "B29") (pinfunction "B29_B29") (pintype "passive"))
      (node (ref "X2") (pin "B29") (pinfunction "B29_B29") (pintype "passive"))
      (node (ref "X3") (pin "B29") (pinfunction "B29_B29") (pintype "passive"))
      (node (ref "X4") (pin "B29") (pinfunction "B29_B29") (pintype "passive"))
      (node (ref "X5") (pin "B29") (pinfunction "B29_B29") (pintype "passive"))
      (node (ref "X6") (pin "B29") (pinfunction "B29_B29") (pintype "passive"))
      (node (ref "X7") (pin "B29") (pinfunction "B29_B29") (pintype "passive"))
    )
    (net (code "78") (name "/SIG77") (class "Default")
      (node (ref "X1") (pin "C29") (pinfunction "C29_C29") (pintype "passive"))
      (node (ref "X2") (pin "C29") (pinfunction "C29_C29") (pintype "passive"))
      (node (ref "X3") (pin "C29") (pinfunction "C29_C29") (pintype "passive"))
      (node (ref "X4") (pin "C29") (pinfunction "C29_C29") (pintype "passive"))
      (node (ref "X5") (pin "C29") (pinfunction "C29_C29") (pintype "passive"))
      (node (ref "X6") (pin "C29") (pinfunction "C29_C29") (pintype "passive"))
      (node (ref "X7") (pin "C29") (pinfunction "C29_C29") (pintype "passive"))
    )
    (net (code "79") (name "/SIG78") (class "Default")
      (node (ref "X1") (pin "A30") (pinfunction "A30_A30") (pintype "passive"))
      (node (ref "X2") (pin "A30") (pinfunction "A30_A30") (pintype "passive"))
      (node (ref "X3") (pin "A30") (pinfunction "A30_A30") (pintype "passive"))
      (node (ref "X4") (pin "A30") (pinfunction "A30_A30") (pintype "passive"))
      (node (ref "X5") (pin "A30") (pinfunction "A30_A30") (pintype "passive"))
      (node (ref "X6") (pin "A30") (pinfunction "A30_A30") (pintype "passive"))
      (node (ref "X7") (pin "A30") (pinfunction "A30_A30") (pintype "passive"))
    )
    (net (code "80") (name "/SIG79") (class "Default")
      (node (ref "X1") (pin "B30") (pinfunction "B30_B30") (pintype "passive"))
      (node (ref "X2") (pin "B30") (pinfunction "B30_B30") (pintype "passive"))
      (node (ref "X3") (pin "B30") (pinfunction "B30_B30") (pintype "passive"))
      (node (ref "X4") (pin "B30") (pinfunction "B30_B30") (pintype "passive"))
      (node (ref "X5") (pin "B30") (pinfunction "B30_B30") (pintype "passive"))
      (node (ref "X6") (pin "B30") (pinfunction "B30_B30") (pintype "passive"))
      (node (ref "X7") (pin "B30") (pinfunction "B30_B30") (pintype "passive"))
    )
    (net (code "81") (name "/SIG80") (class "Default")
      (node (ref "X1") (pin "C30") (pinfunction "C30_C30") (pintype "passive"))
      (node (ref "X2") (pin "C30") (pinfunction "C30_C30") (pintype "passive"))
      (node (ref "X3") (pin "C30") (pinfunction "C30_C30") (pintype "passive"))
      (node (ref "X4") (pin "C30") (pinfunction "C30_C30") (pintype "passive"))
      (node (ref "X5") (pin "C30") (pinfunction "C30_C30") (pintype "passive"))
      (node (ref "X6") (pin "C30") (pinfunction "C30_C30") (pintype "passive"))
      (node (ref "X7") (pin "C30") (pinfunction "C30_C30") (pintype "passive"))
    )
    (net (code "82") (name "/SIG81") (class "Default")
      (node (ref "X1") (pin "A3") (pinfunction "A3_A3") (pintype "passive"))
      (node (ref "X2") (pin "A3") (pinfunction "A3_A3") (pintype "passive"))
      (node (ref "X3") (pin "A3") (pinfunction "A3_A3") (pintype "passive"))
      (node (ref "X4") (pin "A3") (pinfunction "A3_A3") (pintype "passive"))
      (node (ref "X5") (pin "A3") (pinfunction "A3_A3") (pintype "passive"))
      (node (ref "X6") (pin "A3") (pinfunction "A3_A3") (pintype "passive"))
      (node (ref "X7") (pin "A3") (pinfunction "A3_A3") (pintype "passive"))
    )
    (net (code "83") (name "/SIG82") (class "Default")
      (node (ref "X1") (pin "B3") (pinfunction "B3_B3") (pintype "passive"))
      (node (ref "X2") (pin "B3") (pinfunction "B3_B3") (pintype "passive"))
      (node (ref "X3") (pin "B3") (pinfunction "B3_B3") (pintype "passive"))
      (node (ref "X4") (pin "B3") (pinfunction "B3_B3") (pintype "passive"))
      (node (ref "X5") (pin "B3") (pinfunction "B3_B3") (pintype "passive"))
      (node (ref "X6") (pin "B3") (pinfunction "B3_B3") (pintype "passive"))
      (node (ref "X7") (pin "B3") (pinfunction "B3_B3") (pintype "passive"))
    )
    (net (code "84") (name "/SIG83") (class "Default")
      (node (ref "X1") (pin "C3") (pinfunction "C3_C3") (pintype "passive"))
      (node (ref "X2") (pin "C3") (pinfunction "C3_C3") (pintype "passive"))
      (node (ref "X3") (pin "C3") (pinfunction "C3_C3") (pintype "passive"))
      (node (ref "X4") (pin "C3") (pinfunction "C3_C3") (pintype "passive"))
      (node (ref "X5") (pin "C3") (pinfunction "C3_C3") (pintype "passive"))
      (node (ref "X6") (pin "C3") (pinfunction "C3_C3") (pintype "passive"))
      (node (ref "X7") (pin "C3") (pinfunction "C3_C3") (pintype "passive"))
    )
    (net (code "85") (name "5V") (class "Default")
      (node (ref "5V") (pin "1") (pinfunction "P_1") (pintype "passive"))
      (node (ref "C1") (pin "+") (pinfunction "+_+") (pintype "passive"))
      (node (ref "C2") (pin "+") (pinfunction "+_+") (pintype "passive"))
      (node (ref "C3") (pin "+") (pinfunction "+_+") (pintype "passive"))
      (node (ref "C4") (pin "+") (pinfunction "+_+") (pintype "passive"))
      (node (ref "C5") (pin "+") (pinfunction "+_+") (pintype "passive"))
      (node (ref "C6") (pin "+") (pinfunction "+_+") (pintype "passive"))
      (node (ref "R1") (pin "2") (pinfunction "2_2") (pintype "passive"))
      (node (ref "X1") (pin "A2") (pinfunction "A2_A2") (pintype "passive"))
      (node (ref "X1") (pin "A31") (pinfunction "A31_A31") (pintype "passive"))
      (node (ref "X1") (pin "B2") (pinfunction "B2_B2") (pintype "passive"))
      (node (ref "X1") (pin "B31") (pinfunction "B31_B31") (pintype "passive"))
      (node (ref "X1") (pin "C2") (pinfunction "C2_C2") (pintype "passive"))
      (node (ref "X1") (pin "C31") (pinfunction "C31_C31") (pintype "passive"))
      (node (ref "X2") (pin "A2") (pinfunction "A2_A2") (pintype "passive"))
      (node (ref "X2") (pin "A31") (pinfunction "A31_A31") (pintype "passive"))
      (node (ref "X2") (pin "B2") (pinfunction "B2_B2") (pintype "passive"))
      (node (ref "X2") (pin "B31") (pinfunction "B31_B31") (pintype "passive"))
      (node (ref "X2") (pin "C2") (pinfunction "C2_C2") (pintype "passive"))
      (node (ref "X2") (pin "C31") (pinfunction "C31_C31") (pintype "passive"))
      (node (ref "X3") (pin "A2") (pinfunction "A2_A2") (pintype "passive"))
      (node (ref "X3") (pin "A31") (pinfunction "A31_A31") (pintype "passive"))
      (node (ref "X3") (pin "B2") (pinfunction "B2_B2") (pintype "passive"))
      (node (ref "X3") (pin "B31") (pinfunction "B31_B31") (pintype "passive"))
      (node (ref "X3") (pin "C2") (pinfunction "C2_C2") (pintype "passive"))
      (node (ref "X3") (pin "C31") (pinfunction "C31_C31") (pintype "passive"))
      (node (ref "X4") (pin "A2") (pinfunction "A2_A2") (pintype "passive"))
      (node (ref "X4") (pin "A31") (pinfunction "A31_A31") (pintype "passive"))
      (node (ref "X4") (pin "B2") (pinfunction "B2_B2") (pintype "passive"))
      (node (ref "X4") (pin "B31") (pinfunction "B31_B31") (pintype "passive"))
      (node (ref "X4") (pin "C2") (pinfunction "C2_C2") (pintype "passive"))
      (node (ref "X4") (pin "C31") (pinfunction "C31_C31") (pintype "passive"))
      (node (ref "X5") (pin "A2") (pinfunction "A2_A2") (pintype "passive"))
      (node (ref "X5") (pin "A31") (pinfunction "A31_A31") (pintype "passive"))
      (node (ref "X5") (pin "B2") (pinfunction "B2_B2") (pintype "passive"))
      (node (ref "X5") (pin "B31") (pinfunction "B31_B31") (pintype "passive"))
      (node (ref "X5") (pin "C2") (pinfunction "C2_C2") (pintype "passive"))
      (node (ref "X5") (pin "C31") (pinfunction "C31_C31") (pintype "passive"))
      (node (ref "X6") (pin "A2") (pinfunction "A2_A2") (pintype "passive"))
      (node (ref "X6") (pin "A31") (pinfunction "A31_A31") (pintype "passive"))
      (node (ref "X6") (pin "B2") (pinfunction "B2_B2") (pintype "passive"))
      (node (ref "X6") (pin "B31") (pinfunction "B31_B31") (pintype "passive"))
      (node (ref "X6") (pin "C2") (pinfunction "C2_C2") (pintype "passive"))
      (node (ref "X6") (pin "C31") (pinfunction "C31_C31") (pintype "passive"))
      (node (ref "X7") (pin "A2") (pinfunction "A2_A2") (pintype "passive"))
      (node (ref "X7") (pin "A31") (pinfunction "A31_A31") (pintype "passive"))
      (node (ref "X7") (pin "B2") (pinfunction "B2_B2") (pintype "passive"))
      (node (ref "X7") (pin "B31") (pinfunction "B31_B31") (pintype "passive"))
      (node (ref "X7") (pin "C2") (pinfunction "C2_C2") (pintype "passive"))
      (node (ref "X7") (pin "C31") (pinfunction "C31_C31") (pintype "passive"))
    )
    (net (code "86") (name "GND") (class "Default")
      (node (ref "C1") (pin "-") (pinfunction "-_-") (pintype "passive"))
      (node (ref "C2") (pin "-") (pinfunction "-_-") (pintype "passive"))
      (node (ref "C3") (pin "-") (pinfunction "-_-") (pintype "passive"))
      (node (ref "C4") (pin "-") (pinfunction "-_-") (pintype "passive"))
      (node (ref "C5") (pin "-") (pinfunction "-_-") (pintype "passive"))
      (node (ref "C6") (pin "-") (pinfunction "-_-") (pintype "passive"))
      (node (ref "GND") (pin "1") (pinfunction "P_1") (pintype "passive"))
      (node (ref "PWR") (pin "K") (pinfunction "C_K") (pintype "passive"))
      (node (ref "X1") (pin "A1") (pinfunction "A1_A1") (pintype "passive"))
      (node (ref "X1") (pin "A32") (pinfunction "A32_A32") (pintype "passive"))
      (node (ref "X1") (pin "B1") (pinfunction "B1_B1") (pintype "passive"))
      (node (ref "X1") (pin "B32") (pinfunction "B32_B32") (pintype "passive"))
      (node (ref "X1") (pin "C1") (pinfunction "C1_C1") (pintype "passive"))
      (node (ref "X1") (pin "C32") (pinfunction "C32_C32") (pintype "passive"))
      (node (ref "X2") (pin "A1") (pinfunction "A1_A1") (pintype "passive"))
      (node (ref "X2") (pin "A32") (pinfunction "A32_A32") (pintype "passive"))
      (node (ref "X2") (pin "B1") (pinfunction "B1_B1") (pintype "passive"))
      (node (ref "X2") (pin "B32") (pinfunction "B32_B32") (pintype "passive"))
      (node (ref "X2") (pin "C1") (pinfunction "C1_C1") (pintype "passive"))
      (node (ref "X2") (pin "C32") (pinfunction "C32_C32") (pintype "passive"))
      (node (ref "X3") (pin "A1") (pinfunction "A1_A1") (pintype "passive"))
      (node (ref "X3") (pin "A32") (pinfunction "A32_A32") (pintype "passive"))
      (node (ref "X3") (pin "B1") (pinfunction "B1_B1") (pintype "passive"))
      (node (ref "X3") (pin "B32") (pinfunction "B32_B32") (pintype "passive"))
      (node (ref "X3") (pin "C1") (pinfunction "C1_C1") (pintype "passive"))
      (node (ref "X3") (pin "C32") (pinfunction "C32_C32") (pintype "passive"))
      (node (ref "X4") (pin "A1") (pinfunction "A1_A1") (pintype "passive"))
      (node (ref "X4") (pin "A32") (pinfunction "A32_A32") (pintype "passive"))
      (node (ref "X4") (pin "B1") (pinfunction "B1_B1") (pintype "passive"))
      (node (ref "X4") (pin "B32") (pinfunction "B32_B32") (pintype "passive"))
      (node (ref "X4") (pin "C1") (pinfunction "C1_C1") (pintype "passive"))
      (node (ref "X4") (pin "C32") (pinfunction "C32_C32") (pintype "passive"))
      (node (ref "X5") (pin "A1") (pinfunction "A1_A1") (pintype "passive"))
      (node (ref "X5") (pin "A32") (pinfunction "A32_A32") (pintype "passive"))
      (node (ref "X5") (pin "B1") (pinfunction "B1_B1") (pintype "passive"))
      (node (ref "X5") (pin "B32") (pinfunction "B32_B32") (pintype "passive"))
      (node (ref "X5") (pin "C1") (pinfunction "C1_C1") (pintype "passive"))
      (node (ref "X5") (pin "C32") (pinfunction "C32_C32") (pintype "passive"))
      (node (ref "X6") (pin "A1") (pinfunction "A1_A1") (pintype "passive"))
      (node (ref "X6") (pin "A32") (pinfunction "A32_A32") (pintype "passive"))
      (node (ref "X6") (pin "B1") (pinfunction "B1_B1") (pintype "passive"))
      (node (ref "X6") (pin "B32") (pinfunction "B32_B32") (pintype "passive"))
      (node (ref "X6") (pin "C1") (pinfunction "C1_C1") (pintype "passive"))
      (node (ref "X6") (pin "C32") (pinfunction "C32_C32") (pintype "passive"))
      (node (ref "X7") (pin "A1") (pinfunction "A1_A1") (pintype "passive"))
      (node (ref "X7") (pin "A32") (pinfunction "A32_A32") (pintype "passive"))
      (node (ref "X7") (pin "B1") (pinfunction "B1_B1") (pintype "passive"))
      (node (ref "X7") (pin "B32") (pinfunction "B32_B32") (pintype "passive"))
      (node (ref "X7") (pin "C1") (pinfunction "C1_C1") (pintype "passive"))
      (node (ref "X7") (pin "C32") (pinfunction "C32_C32") (pintype "passive"))
    )
    (net (code "87") (name "Net-(PWR-PadA)") (class "Default")
      (node (ref "PWR") (pin "A") (pinfunction "A_A") (pintype "passive"))
      (node (ref "R1") (pin "1") (pinfunction "1_1") (pintype "passive"))
    )
  )
)
